# Gen7AdapterBoard.net
KiCad netlist of a schematic drawn in EAGLE
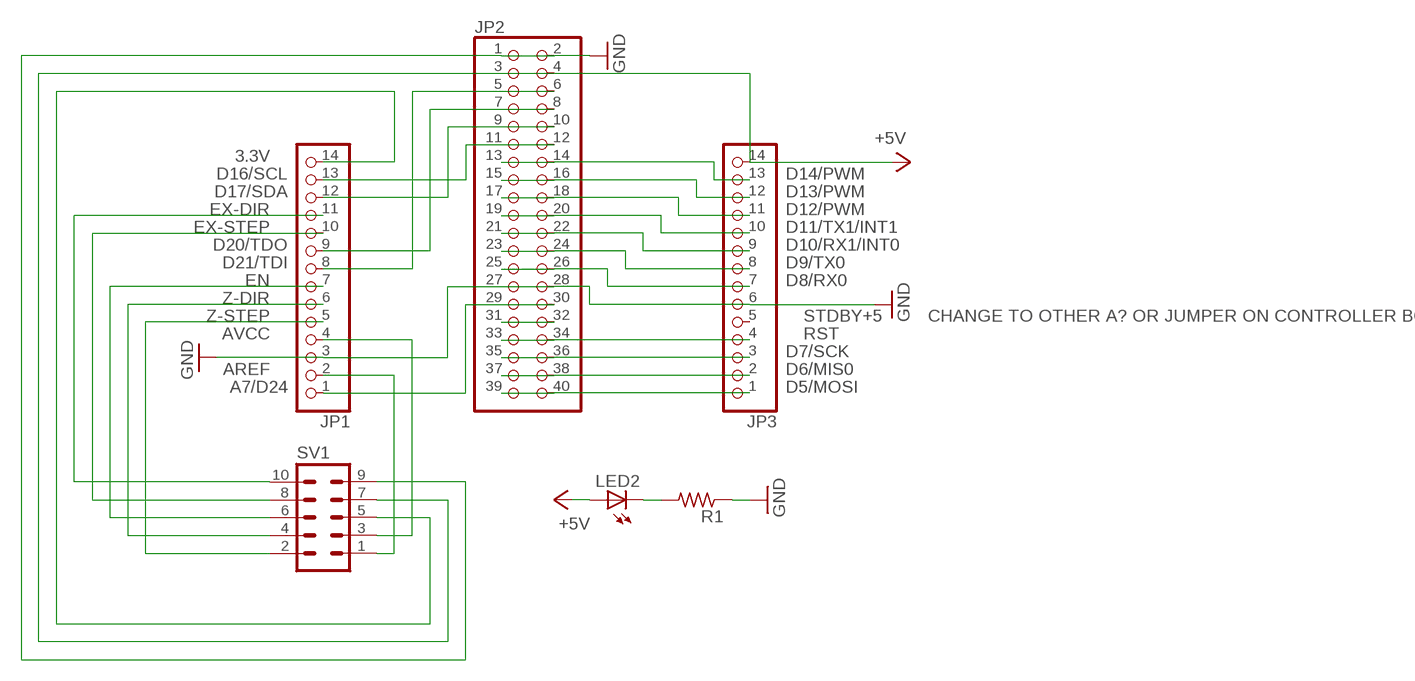
[diagram p0: schematic, sheet 1]

(export (version "E")
  (design (tool "Eeschema 10.0.6"))
  (components
    (comp (ref "JP1")
      (value "PINHD-1X14")
      (footprint "eagle-import:1X14")
      (libsource (lib "eagle-import") (part "PINHD-1X14"))
    )
    (comp (ref "JP2")
      (value "PINHD-2X20")
      (footprint "eagle-import:2X20")
      (libsource (lib "eagle-import") (part "PINHD-2X20"))
    )
    (comp (ref "JP3")
      (value "PINHD-1X14")
      (footprint "eagle-import:1X14")
      (libsource (lib "eagle-import") (part "PINHD-1X14"))
    )
    (comp (ref "LED2")
      (value "LED5MM")
      (footprint "eagle-import:LED5MM")
      (libsource (lib "eagle-import") (part "LED5MM"))
    )
    (comp (ref "R1")
      (value "R-US_0207/10")
      (footprint "eagle-import:0207_10")
      (libsource (lib "eagle-import") (part "R-US_0207/10"))
    )
    (comp (ref "SV1")
      (value "MA05-2")
      (footprint "eagle-import:MA05-2")
      (libsource (lib "eagle-import") (part "MA05-2"))
    )
  )
  (nets
    (net (code "1") (name "+5V") (class "Default")
      (node (ref "JP2") (pin "3") (pinfunction "3_3") (pintype "passive"))
      (node (ref "JP2") (pin "4") (pinfunction "4_4") (pintype "passive"))
      (node (ref "JP3") (pin "14") (pinfunction "14_14") (pintype "passive"))
      (node (ref "LED2") (pin "A") (pinfunction "A_A") (pintype "passive"))
      (node (ref "SV1") (pin "7") (pinfunction "7_7") (pintype "passive"))
    )
    (net (code "2") (name "GND") (class "Default")
      (node (ref "JP1") (pin "3") (pinfunction "3_3") (pintype "passive"))
      (node (ref "JP2") (pin "1") (pinfunction "1_1") (pintype "passive"))
      (node (ref "JP2") (pin "2") (pinfunction "2_2") (pintype "passive"))
      (node (ref "JP2") (pin "27") (pinfunction "27_27") (pintype "passive"))
      (node (ref "JP2") (pin "28") (pinfunction "28_28") (pintype "passive"))
      (node (ref "JP3") (pin "6") (pinfunction "6_6") (pintype "passive"))
      (node (ref "R1") (pin "1") (pinfunction "1_1") (pintype "passive"))
      (node (ref "SV1") (pin "9") (pinfunction "9_9") (pintype "passive"))
    )
    (net (code "3") (name "Net-(JP1-Pad1)") (class "Default")
      (node (ref "JP1") (pin "1") (pinfunction "1_1") (pintype "passive"))
      (node (ref "JP2") (pin "29") (pinfunction "29_29") (pintype "passive"))
      (node (ref "JP2") (pin "30") (pinfunction "30_30") (pintype "passive"))
    )
    (net (code "4") (name "Net-(JP1-Pad2)") (class "Default")
      (node (ref "JP1") (pin "2") (pinfunction "2_2") (pintype "passive"))
      (node (ref "SV1") (pin "1") (pinfunction "1_1") (pintype "passive"))
    )
    (net (code "5") (name "Net-(JP1-Pad4)") (class "Default")
      (node (ref "JP1") (pin "4") (pinfunction "4_4") (pintype "passive"))
      (node (ref "SV1") (pin "3") (pinfunction "3_3") (pintype "passive"))
    )
    (net (code "6") (name "Net-(JP1-Pad5)") (class "Default")
      (node (ref "JP1") (pin "5") (pinfunction "5_5") (pintype "passive"))
      (node (ref "SV1") (pin "2") (pinfunction "2_2") (pintype "passive"))
    )
    (net (code "7") (name "Net-(JP1-Pad6)") (class "Default")
      (node (ref "JP1") (pin "6") (pinfunction "6_6") (pintype "passive"))
      (node (ref "SV1") (pin "4") (pinfunction "4_4") (pintype "passive"))
    )
    (net (code "8") (name "Net-(JP1-Pad7)") (class "Default")
      (node (ref "JP1") (pin "7") (pinfunction "7_7") (pintype "passive"))
      (node (ref "SV1") (pin "6") (pinfunction "6_6") (pintype "passive"))
    )
    (net (code "9") (name "Net-(JP1-Pad8)") (class "Default")
      (node (ref "JP1") (pin "8") (pinfunction "8_8") (pintype "passive"))
      (node (ref "JP2") (pin "5") (pinfunction "5_5") (pintype "passive"))
      (node (ref "JP2") (pin "6") (pinfunction "6_6") (pintype "passive"))
    )
    (net (code "10") (name "Net-(JP1-Pad9)") (class "Default")
      (node (ref "JP1") (pin "9") (pinfunction "9_9") (pintype "passive"))
      (node (ref "JP2") (pin "7") (pinfunction "7_7") (pintype "passive"))
      (node (ref "JP2") (pin "8") (pinfunction "8_8") (pintype "passive"))
    )
    (net (code "11") (name "Net-(JP1-Pad10)") (class "Default")
      (node (ref "JP1") (pin "10") (pinfunction "10_10") (pintype "passive"))
      (node (ref "SV1") (pin "8") (pinfunction "8_8") (pintype "passive"))
    )
    (net (code "12") (name "Net-(JP1-Pad11)") (class "Default")
      (node (ref "JP1") (pin "11") (pinfunction "11_11") (pintype "passive"))
      (node (ref "SV1") (pin "10") (pinfunction "10_10") (pintype "passive"))
    )
    (net (code "13") (name "Net-(JP1-Pad12)") (class "Default")
      (node (ref "JP1") (pin "12") (pinfunction "12_12") (pintype "passive"))
      (node (ref "JP2") (pin "10") (pinfunction "10_10") (pintype "passive"))
      (node (ref "JP2") (pin "9") (pinfunction "9_9") (pintype "passive"))
    )
    (net (code "14") (name "Net-(JP1-Pad13)") (class "Default")
      (node (ref "JP1") (pin "13") (pinfunction "13_13") (pintype "passive"))
      (node (ref "JP2") (pin "11") (pinfunction "11_11") (pintype "passive"))
      (node (ref "JP2") (pin "12") (pinfunction "12_12") (pintype "passive"))
    )
    (net (code "15") (name "Net-(JP1-Pad14)") (class "Default")
      (node (ref "JP1") (pin "14") (pinfunction "14_14") (pintype "passive"))
      (node (ref "SV1") (pin "5") (pinfunction "5_5") (pintype "passive"))
    )
    (net (code "16") (name "Net-(JP2-Pad13)") (class "Default")
      (node (ref "JP2") (pin "13") (pinfunction "13_13") (pintype "passive"))
      (node (ref "JP2") (pin "14") (pinfunction "14_14") (pintype "passive"))
      (node (ref "JP3") (pin "13") (pinfunction "13_13") (pintype "passive"))
    )
    (net (code "17") (name "Net-(JP2-Pad15)") (class "Default")
      (node (ref "JP2") (pin "15") (pinfunction "15_15") (pintype "passive"))
      (node (ref "JP2") (pin "16") (pinfunction "16_16") (pintype "passive"))
      (node (ref "JP3") (pin "12") (pinfunction "12_12") (pintype "passive"))
    )
    (net (code "18") (name "Net-(JP2-Pad17)") (class "Default")
      (node (ref "JP2") (pin "17") (pinfunction "17_17") (pintype "passive"))
      (node (ref "JP2") (pin "18") (pinfunction "18_18") (pintype "passive"))
      (node (ref "JP3") (pin "11") (pinfunction "11_11") (pintype "passive"))
    )
    (net (code "19") (name "Net-(JP2-Pad19)") (class "Default")
      (node (ref "JP2") (pin "19") (pinfunction "19_19") (pintype "passive"))
      (node (ref "JP2") (pin "20") (pinfunction "20_20") (pintype "passive"))
      (node (ref "JP3") (pin "10") (pinfunction "10_10") (pintype "passive"))
    )
    (net (code "20") (name "Net-(JP2-Pad21)") (class "Default")
      (node (ref "JP2") (pin "21") (pinfunction "21_21") (pintype "passive"))
      (node (ref "JP2") (pin "22") (pinfunction "22_22") (pintype "passive"))
      (node (ref "JP3") (pin "9") (pinfunction "9_9") (pintype "passive"))
    )
    (net (code "21") (name "Net-(JP2-Pad23)") (class "Default")
      (node (ref "JP2") (pin "23") (pinfunction "23_23") (pintype "passive"))
      (node (ref "JP2") (pin "24") (pinfunction "24_24") (pintype "passive"))
      (node (ref "JP3") (pin "8") (pinfunction "8_8") (pintype "passive"))
    )
    (net (code "22") (name "Net-(JP2-Pad25)") (class "Default")
      (node (ref "JP2") (pin "25") (pinfunction "25_25") (pintype "passive"))
      (node (ref "JP2") (pin "26") (pinfunction "26_26") (pintype "passive"))
      (node (ref "JP3") (pin "7") (pinfunction "7_7") (pintype "passive"))
    )
    (net (code "23") (name "Net-(JP2-Pad31)") (class "Default")
      (node (ref "JP2") (pin "31") (pinfunction "31_31") (pintype "passive"))
      (node (ref "JP2") (pin "32") (pinfunction "32_32") (pintype "passive"))
    )
    (net (code "24") (name "Net-(JP2-Pad33)") (class "Default")
      (node (ref "JP2") (pin "33") (pinfunction "33_33") (pintype "passive"))
      (node (ref "JP2") (pin "34") (pinfunction "34_34") (pintype "passive"))
      (node (ref "JP3") (pin "4") (pinfunction "4_4") (pintype "passive"))
    )
    (net (code "25") (name "Net-(JP2-Pad35)") (class "Default")
      (node (ref "JP2") (pin "35") (pinfunction "35_35") (pintype "passive"))
      (node (ref "JP2") (pin "36") (pinfunction "36_36") (pintype "passive"))
      (node (ref "JP3") (pin "3") (pinfunction "3_3") (pintype "passive"))
    )
    (net (code "26") (name "Net-(JP2-Pad37)") (class "Default")
      (node (ref "JP2") (pin "37") (pinfunction "37_37") (pintype "passive"))
      (node (ref "JP2") (pin "38") (pinfunction "38_38") (pintype "passive"))
      (node (ref "JP3") (pin "2") (pinfunction "2_2") (pintype "passive"))
    )
    (net (code "27") (name "Net-(JP2-Pad39)") (class "Default")
      (node (ref "JP2") (pin "39") (pinfunction "39_39") (pintype "passive"))
      (node (ref "JP2") (pin "40") (pinfunction "40_40") (pintype "passive"))
      (node (ref "JP3") (pin "1") (pinfunction "1_1") (pintype "passive"))
    )
    (net (code "28") (name "Net-(LED2-C)") (class "Default")
      (node (ref "LED2") (pin "K") (pinfunction "C_K") (pintype "passive"))
      (node (ref "R1") (pin "2") (pinfunction "2_2") (pintype "passive"))
    )
    (net (code "29") (name "unconnected-(JP3-Pad5)") (class "Default")
      (node (ref "JP3") (pin "5") (pinfunction "5_5") (pintype "passive"))
    )
  )
)
